# Qwiic_Shield_for_Teensy_Long.net
KiCad netlist of a schematic drawn in EAGLE
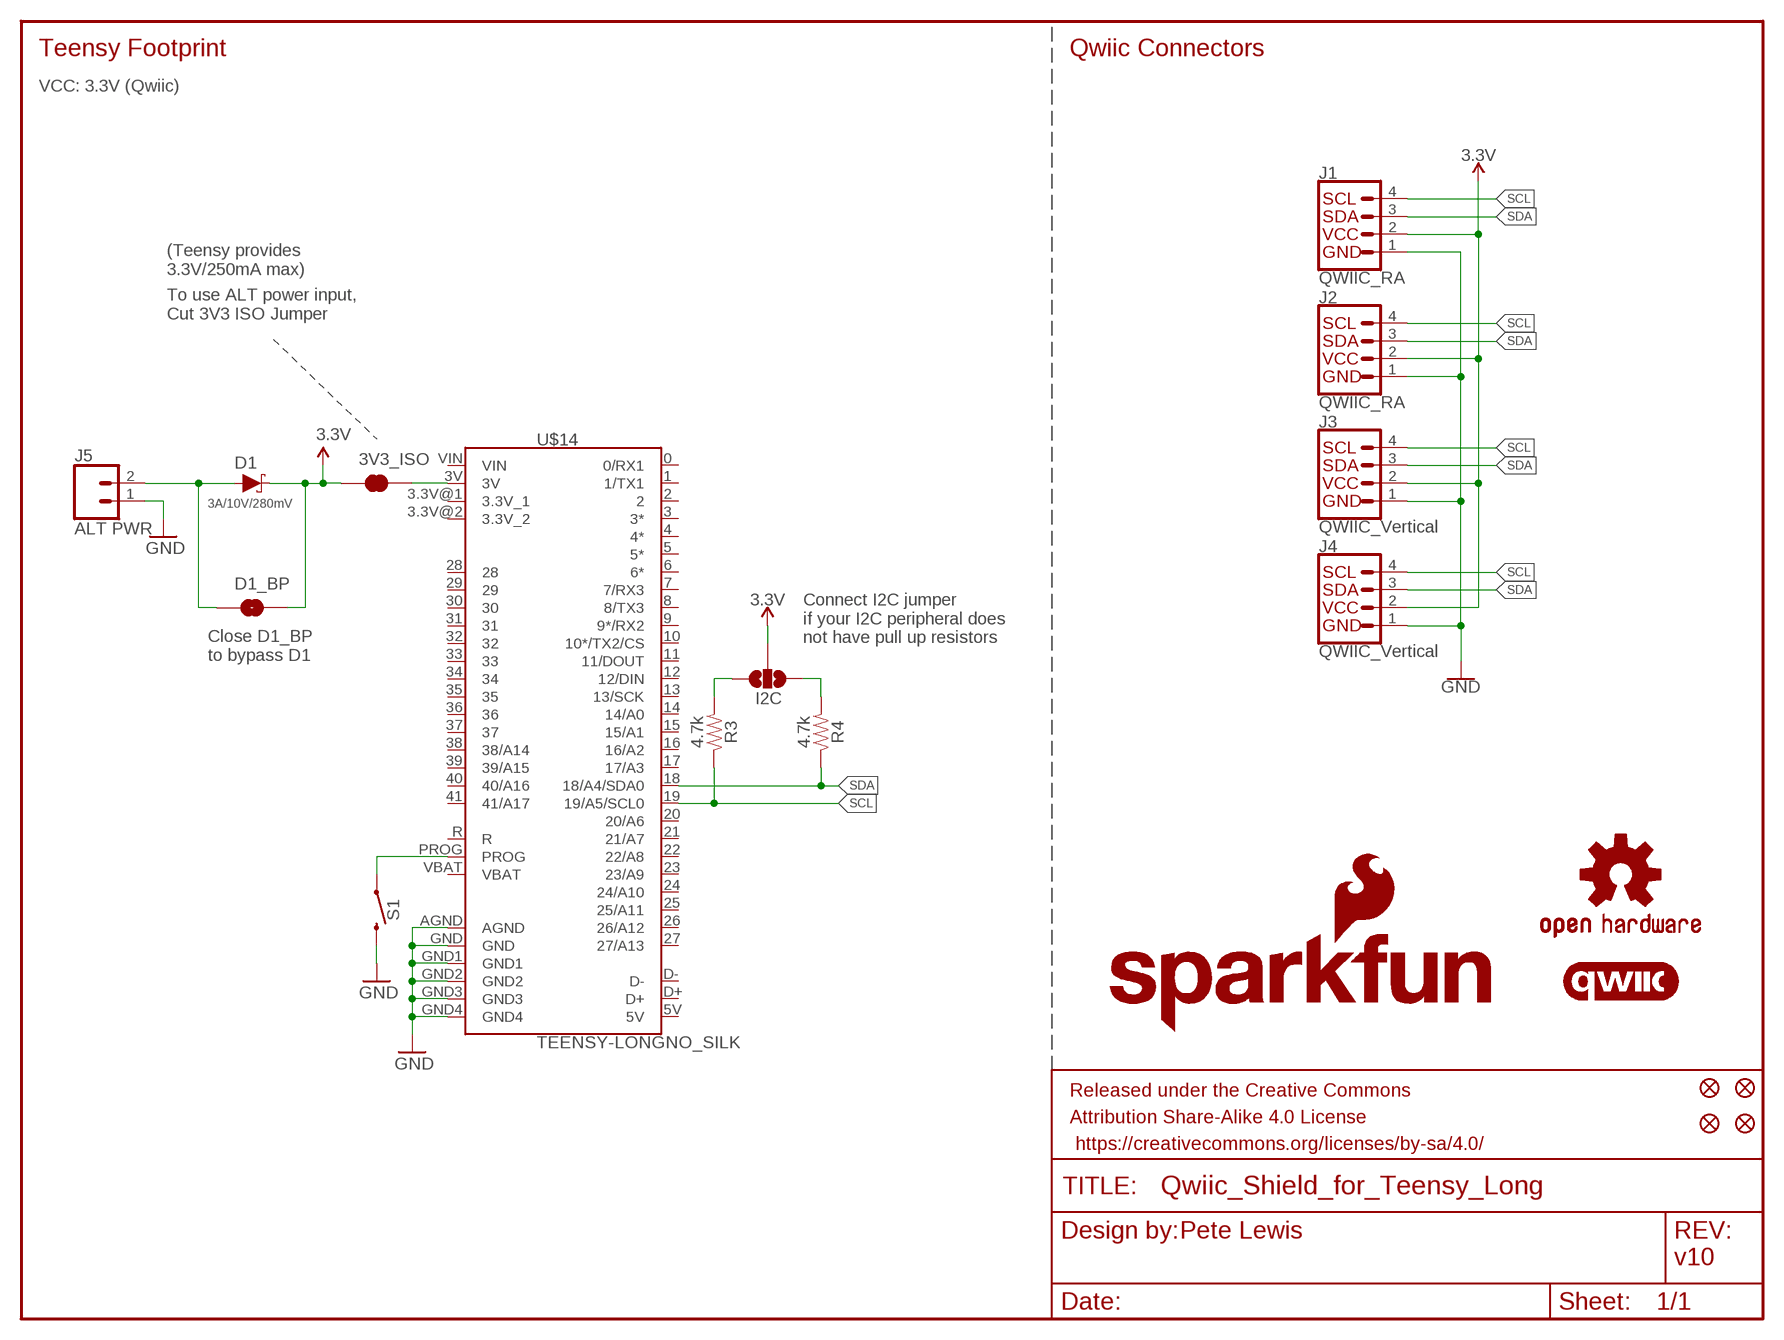
[diagram p0: schematic, sheet 1]

(export (version "E")
  (design (tool "Eeschema 10.0.6"))
  (components
    (comp (ref "3V3_ISO")
      (value "JUMPER-SMT_2_NC_TRACE_SILK")
      (footprint "eagle-import:SMT-JUMPER_2_NC_TRACE_SILK")
      (libsource (lib "eagle-import") (part "JUMPER-SMT_2_NC_TRACE_SILK"))
    )
    (comp (ref "D1")
      (value "3A/10V/280mV")
      (footprint "eagle-import:SOD-323")
      (libsource (lib "eagle-import") (part "DIODE-SCHOTTKY-BAT60A"))
    )
    (comp (ref "D1_BP")
      (value "JUMPER-SMT_2_NO_SILK")
      (footprint "eagle-import:SMT-JUMPER_2_NO_SILK")
      (libsource (lib "eagle-import") (part "JUMPER-SMT_2_NO_SILK"))
    )
    (comp (ref "FD1")
      (value "FIDUCIAL1X2")
      (footprint "eagle-import:FIDUCIAL-1X2")
      (libsource (lib "eagle-import") (part "FIDUCIAL1X2"))
    )
    (comp (ref "FD2")
      (value "FIDUCIAL1X2")
      (footprint "eagle-import:FIDUCIAL-1X2")
      (libsource (lib "eagle-import") (part "FIDUCIAL1X2"))
    )
    (comp (ref "FD3")
      (value "FIDUCIAL1X2")
      (footprint "eagle-import:FIDUCIAL-1X2")
      (libsource (lib "eagle-import") (part "FIDUCIAL1X2"))
    )
    (comp (ref "FD4")
      (value "FIDUCIAL1X2")
      (footprint "eagle-import:FIDUCIAL-1X2")
      (libsource (lib "eagle-import") (part "FIDUCIAL1X2"))
    )
    (comp (ref "FRAME1")
      (value "FRAME-LETTER")
      (footprint "eagle-import:CREATIVE_COMMONS")
      (libsource (lib "eagle-import") (part "FRAME-LETTER"))
    )
    (comp (ref "I2C")
      (value "JUMPER-SMT_3_NO_SILK")
      (footprint "eagle-import:SMT-JUMPER_3_NO_SILK")
      (libsource (lib "eagle-import") (part "JUMPER-SMT_3_NO_SILK"))
    )
    (comp (ref "J1")
      (value "QWIIC_RA")
      (footprint "eagle-import:JST04_1MM_RA")
      (libsource (lib "eagle-import") (part "QWIIC_CONNECTORJS-1MM"))
    )
    (comp (ref "J2")
      (value "QWIIC_RA")
      (footprint "eagle-import:JST04_1MM_RA")
      (libsource (lib "eagle-import") (part "QWIIC_CONNECTORJS-1MM"))
    )
    (comp (ref "J3")
      (value "QWIIC_Vertical")
      (footprint "eagle-import:JST04_1MM_VERT")
      (libsource (lib "eagle-import") (part "QWIIC_CONNECTOR"))
    )
    (comp (ref "J4")
      (value "QWIIC_Vertical")
      (footprint "eagle-import:JST04_1MM_VERT")
      (libsource (lib "eagle-import") (part "QWIIC_CONNECTOR"))
    )
    (comp (ref "J5")
      (value "ALT PWR")
      (footprint "eagle-import:1X02_NO_SILK")
      (libsource (lib "eagle-import") (part "CONN_021X02_NO_SILK"))
    )
    (comp (ref "LOGO1")
      (value "SFE_LOGO_NAME_FLAME.1_INCH")
      (footprint "eagle-import:SFE_LOGO_NAME_FLAME_.1")
      (libsource (lib "eagle-import") (part "SFE_LOGO_NAME_FLAME.1_INCH"))
    )
    (comp (ref "LOGO2")
      (value "SFE_LOGO_NAME_FLAME.1_INCH")
      (footprint "eagle-import:SFE_LOGO_NAME_FLAME_.1")
      (libsource (lib "eagle-import") (part "SFE_LOGO_NAME_FLAME.1_INCH"))
    )
    (comp (ref "LOGO3")
      (value "OSHW-LOGOS")
      (footprint "eagle-import:OSHW-LOGO-S")
      (libsource (lib "eagle-import") (part "OSHW-LOGOS"))
    )
    (comp (ref "LOGO4")
      (value "QWIIC_LOGO_5MM")
      (footprint "eagle-import:QWIIC_5MM")
      (libsource (lib "eagle-import") (part "QWIIC_LOGO_5MM"))
    )
    (comp (ref "LOGO5")
      (value "QWIIC_LOGO_5MM")
      (footprint "eagle-import:QWIIC_5MM")
      (libsource (lib "eagle-import") (part "QWIIC_LOGO_5MM"))
    )
    (comp (ref "R3")
      (value "4.7k")
      (footprint "eagle-import:0603")
      (libsource (lib "eagle-import") (part "4.7KOHM-0603-1/10W-1%"))
    )
    (comp (ref "R4")
      (value "4.7k")
      (footprint "eagle-import:0603")
      (libsource (lib "eagle-import") (part "4.7KOHM-0603-1/10W-1%"))
    )
    (comp (ref "S1")
      (value "MOMENTARY-SWITCH-SPST-SMD-5.2MM-TALL")
      (footprint "eagle-import:TACTILE_SWITCH_SMD_5.2MM")
      (libsource (lib "eagle-import") (part "MOMENTARY-SWITCH-SPST-SMD-5.2MM-TALL"))
    )
    (comp (ref "U$14")
      (value "TEENSY-LONGNO_SILK")
      (footprint "eagle-import:TEENSY-LONG_NO_SILK")
      (libsource (lib "eagle-import") (part "TEENSY-LONGNO_SILK"))
    )
  )
  (nets
    (net (code "1") (name "/3.3V_1") (class "Default")
      (node (ref "U$14") (pin "3.3V@1") (pinfunction "3.3V_1_3.3V@1") (pintype "power_in"))
    )
    (net (code "2") (name "/3.3V_2") (class "Default")
      (node (ref "U$14") (pin "3.3V@2") (pinfunction "3.3V_2_3.3V@2") (pintype "power_in"))
    )
    (net (code "3") (name "/5V") (class "Default")
      (node (ref "U$14") (pin "5V") (pinfunction "5V_5V") (pintype "power_in"))
    )
    (net (code "4") (name "/D+") (class "Default")
      (node (ref "U$14") (pin "D+") (pinfunction "D+_D+") (pintype "power_in"))
    )
    (net (code "5") (name "/D-") (class "Default")
      (node (ref "U$14") (pin "D-") (pinfunction "D-_D-") (pintype "power_in"))
    )
    (net (code "6") (name "/VBAT") (class "Default")
      (node (ref "U$14") (pin "VBAT") (pinfunction "VBAT_VBAT") (pintype "power_in"))
    )
    (net (code "7") (name "/VIN") (class "Default")
      (node (ref "U$14") (pin "VIN") (pinfunction "VIN_VIN") (pintype "power_in"))
    )
    (net (code "8") (name "3.3V") (class "Default")
      (node (ref "3V3_ISO") (pin "1") (pinfunction "1_1") (pintype "passive"))
      (node (ref "D1") (pin "C") (pinfunction "C_C") (pintype "passive"))
      (node (ref "D1_BP") (pin "2") (pinfunction "2_2") (pintype "passive"))
      (node (ref "I2C") (pin "2") (pinfunction "2_2") (pintype "passive"))
      (node (ref "J1") (pin "2") (pinfunction "2_2") (pintype "power_in"))
      (node (ref "J2") (pin "2") (pinfunction "2_2") (pintype "power_in"))
      (node (ref "J3") (pin "2") (pinfunction "2_2") (pintype "power_in"))
      (node (ref "J4") (pin "2") (pinfunction "2_2") (pintype "power_in"))
    )
    (net (code "9") (name "GND") (class "Default")
      (node (ref "J1") (pin "1") (pinfunction "1_1") (pintype "power_in"))
      (node (ref "J2") (pin "1") (pinfunction "1_1") (pintype "power_in"))
      (node (ref "J3") (pin "1") (pinfunction "1_1") (pintype "power_in"))
      (node (ref "J4") (pin "1") (pinfunction "1_1") (pintype "power_in"))
      (node (ref "J5") (pin "1") (pinfunction "1_1") (pintype "passive"))
      (node (ref "S1") (pin "3") (pinfunction "2_3") (pintype "passive"))
      (node (ref "U$14") (pin "AGND") (pinfunction "AGND_AGND") (pintype "power_in"))
      (node (ref "U$14") (pin "GND") (pinfunction "GND_GND") (pintype "power_in"))
      (node (ref "U$14") (pin "GND1") (pinfunction "GND1_GND1") (pintype "power_in"))
      (node (ref "U$14") (pin "GND2") (pinfunction "GND2_GND2") (pintype "power_in"))
      (node (ref "U$14") (pin "GND3") (pinfunction "GND3_GND3") (pintype "power_in"))
      (node (ref "U$14") (pin "GND4") (pinfunction "GND4_GND4") (pintype "bidirectional"))
    )
    (net (code "10") (name "Net-(3V3_ISO-Pad2)") (class "Default")
      (node (ref "3V3_ISO") (pin "2") (pinfunction "2_2") (pintype "passive"))
      (node (ref "U$14") (pin "3V") (pinfunction "3V_3V") (pintype "power_in"))
    )
    (net (code "11") (name "Net-(D1-PadA)") (class "Default")
      (node (ref "D1") (pin "A") (pinfunction "A_A") (pintype "passive"))
      (node (ref "D1_BP") (pin "1") (pinfunction "1_1") (pintype "passive"))
      (node (ref "J5") (pin "2") (pinfunction "2_2") (pintype "passive"))
    )
    (net (code "12") (name "Net-(I2C-Pad1)") (class "Default")
      (node (ref "I2C") (pin "1") (pinfunction "1_1") (pintype "passive"))
      (node (ref "R3") (pin "2") (pinfunction "2_2") (pintype "passive"))
    )
    (net (code "13") (name "Net-(I2C-Pad3)") (class "Default")
      (node (ref "I2C") (pin "3") (pinfunction "3_3") (pintype "passive"))
      (node (ref "R4") (pin "2") (pinfunction "2_2") (pintype "passive"))
    )
    (net (code "14") (name "Net-(S1-Pad1)") (class "Default")
      (node (ref "S1") (pin "1") (pinfunction "1_1") (pintype "passive"))
      (node (ref "U$14") (pin "PROG") (pinfunction "PROG_PROG") (pintype "bidirectional"))
    )
    (net (code "15") (name "SCL") (class "Default")
      (node (ref "J1") (pin "4") (pinfunction "4_4") (pintype "passive"))
      (node (ref "J2") (pin "4") (pinfunction "4_4") (pintype "passive"))
      (node (ref "J3") (pin "4") (pinfunction "4_4") (pintype "passive"))
      (node (ref "J4") (pin "4") (pinfunction "4_4") (pintype "passive"))
      (node (ref "R3") (pin "1") (pinfunction "1_1") (pintype "passive"))
      (node (ref "U$14") (pin "19") (pinfunction "19/A5/SCL0_19") (pintype "bidirectional"))
    )
    (net (code "16") (name "SDA") (class "Default")
      (node (ref "J1") (pin "3") (pinfunction "3_3") (pintype "passive"))
      (node (ref "J2") (pin "3") (pinfunction "3_3") (pintype "passive"))
      (node (ref "J3") (pin "3") (pinfunction "3_3") (pintype "passive"))
      (node (ref "J4") (pin "3") (pinfunction "3_3") (pintype "passive"))
      (node (ref "R4") (pin "1") (pinfunction "1_1") (pintype "passive"))
      (node (ref "U$14") (pin "18") (pinfunction "18/A4/SDA0_18") (pintype "bidirectional"))
    )
    (net (code "17") (name "unconnected-(U$14-0{slash}RX1-Pad0)") (class "Default")
      (node (ref "U$14") (pin "0") (pinfunction "0/RX1_0") (pintype "bidirectional"))
    )
    (net (code "18") (name "unconnected-(U$14-1{slash}TX1-Pad1)") (class "Default")
      (node (ref "U$14") (pin "1") (pinfunction "1/TX1_1") (pintype "bidirectional"))
    )
    (net (code "19") (name "unconnected-(U$14-3*-Pad3)") (class "Default")
      (node (ref "U$14") (pin "3") (pinfunction "3*_3") (pintype "bidirectional"))
    )
    (net (code "20") (name "unconnected-(U$14-4*-Pad4)") (class "Default")
      (node (ref "U$14") (pin "4") (pinfunction "4*_4") (pintype "bidirectional"))
    )
    (net (code "21") (name "unconnected-(U$14-5*-Pad5)") (class "Default")
      (node (ref "U$14") (pin "5") (pinfunction "5*_5") (pintype "bidirectional"))
    )
    (net (code "22") (name "unconnected-(U$14-6*-Pad6)") (class "Default")
      (node (ref "U$14") (pin "6") (pinfunction "6*_6") (pintype "bidirectional"))
    )
    (net (code "23") (name "unconnected-(U$14-7{slash}RX3-Pad7)") (class "Default")
      (node (ref "U$14") (pin "7") (pinfunction "7/RX3_7") (pintype "bidirectional"))
    )
    (net (code "24") (name "unconnected-(U$14-8{slash}TX3-Pad8)") (class "Default")
      (node (ref "U$14") (pin "8") (pinfunction "8/TX3_8") (pintype "bidirectional"))
    )
    (net (code "25") (name "unconnected-(U$14-9*{slash}RX2-Pad9)") (class "Default")
      (node (ref "U$14") (pin "9") (pinfunction "9*/RX2_9") (pintype "bidirectional"))
    )
    (net (code "26") (name "unconnected-(U$14-10*{slash}TX2{slash}CS-Pad10)") (class "Default")
      (node (ref "U$14") (pin "10") (pinfunction "10*/TX2/CS_10") (pintype "bidirectional"))
    )
    (net (code "27") (name "unconnected-(U$14-11{slash}DOUT-Pad11)") (class "Default")
      (node (ref "U$14") (pin "11") (pinfunction "11/DOUT_11") (pintype "bidirectional"))
    )
    (net (code "28") (name "unconnected-(U$14-12{slash}DIN-Pad12)") (class "Default")
      (node (ref "U$14") (pin "12") (pinfunction "12/DIN_12") (pintype "bidirectional"))
    )
    (net (code "29") (name "unconnected-(U$14-13{slash}SCK-Pad13)") (class "Default")
      (node (ref "U$14") (pin "13") (pinfunction "13/SCK_13") (pintype "bidirectional"))
    )
    (net (code "30") (name "unconnected-(U$14-14{slash}A0-Pad14)") (class "Default")
      (node (ref "U$14") (pin "14") (pinfunction "14/A0_14") (pintype "bidirectional"))
    )
    (net (code "31") (name "unconnected-(U$14-15{slash}A1-Pad15)") (class "Default")
      (node (ref "U$14") (pin "15") (pinfunction "15/A1_15") (pintype "bidirectional"))
    )
    (net (code "32") (name "unconnected-(U$14-16{slash}A2-Pad16)") (class "Default")
      (node (ref "U$14") (pin "16") (pinfunction "16/A2_16") (pintype "bidirectional"))
    )
    (net (code "33") (name "unconnected-(U$14-17{slash}A3-Pad17)") (class "Default")
      (node (ref "U$14") (pin "17") (pinfunction "17/A3_17") (pintype "bidirectional"))
    )
    (net (code "34") (name "unconnected-(U$14-20{slash}A6-Pad20)") (class "Default")
      (node (ref "U$14") (pin "20") (pinfunction "20/A6_20") (pintype "bidirectional"))
    )
    (net (code "35") (name "unconnected-(U$14-21{slash}A7-Pad21)") (class "Default")
      (node (ref "U$14") (pin "21") (pinfunction "21/A7_21") (pintype "bidirectional"))
    )
    (net (code "36") (name "unconnected-(U$14-22{slash}A8-Pad22)") (class "Default")
      (node (ref "U$14") (pin "22") (pinfunction "22/A8_22") (pintype "bidirectional"))
    )
    (net (code "37") (name "unconnected-(U$14-23{slash}A9-Pad23)") (class "Default")
      (node (ref "U$14") (pin "23") (pinfunction "23/A9_23") (pintype "bidirectional"))
    )
    (net (code "38") (name "unconnected-(U$14-24{slash}A10-Pad24)") (class "Default")
      (node (ref "U$14") (pin "24") (pinfunction "24/A10_24") (pintype "bidirectional"))
    )
    (net (code "39") (name "unconnected-(U$14-25{slash}A11-Pad25)") (class "Default")
      (node (ref "U$14") (pin "25") (pinfunction "25/A11_25") (pintype "bidirectional"))
    )
    (net (code "40") (name "unconnected-(U$14-26{slash}A12-Pad26)") (class "Default")
      (node (ref "U$14") (pin "26") (pinfunction "26/A12_26") (pintype "bidirectional"))
    )
    (net (code "41") (name "unconnected-(U$14-27{slash}A13-Pad27)") (class "Default")
      (node (ref "U$14") (pin "27") (pinfunction "27/A13_27") (pintype "bidirectional"))
    )
    (net (code "42") (name "unconnected-(U$14-38{slash}A14-Pad38)") (class "Default")
      (node (ref "U$14") (pin "38") (pinfunction "38/A14_38") (pintype "bidirectional"))
    )
    (net (code "43") (name "unconnected-(U$14-39{slash}A15-Pad39)") (class "Default")
      (node (ref "U$14") (pin "39") (pinfunction "39/A15_39") (pintype "bidirectional"))
    )
    (net (code "44") (name "unconnected-(U$14-40{slash}A16-Pad40)") (class "Default")
      (node (ref "U$14") (pin "40") (pinfunction "40/A16_40") (pintype "bidirectional"))
    )
    (net (code "45") (name "unconnected-(U$14-41{slash}A17-Pad41)") (class "Default")
      (node (ref "U$14") (pin "41") (pinfunction "41/A17_41") (pintype "bidirectional"))
    )
    (net (code "46") (name "unconnected-(U$14-Pad2)") (class "Default")
      (node (ref "U$14") (pin "2") (pinfunction "2_2") (pintype "bidirectional"))
    )
    (net (code "47") (name "unconnected-(U$14-Pad28)") (class "Default")
      (node (ref "U$14") (pin "28") (pinfunction "28_28") (pintype "bidirectional"))
    )
    (net (code "48") (name "unconnected-(U$14-Pad29)") (class "Default")
      (node (ref "U$14") (pin "29") (pinfunction "29_29") (pintype "bidirectional"))
    )
    (net (code "49") (name "unconnected-(U$14-Pad30)") (class "Default")
      (node (ref "U$14") (pin "30") (pinfunction "30_30") (pintype "bidirectional"))
    )
    (net (code "50") (name "unconnected-(U$14-Pad31)") (class "Default")
      (node (ref "U$14") (pin "31") (pinfunction "31_31") (pintype "bidirectional"))
    )
    (net (code "51") (name "unconnected-(U$14-Pad32)") (class "Default")
      (node (ref "U$14") (pin "32") (pinfunction "32_32") (pintype "bidirectional"))
    )
    (net (code "52") (name "unconnected-(U$14-Pad33)") (class "Default")
      (node (ref "U$14") (pin "33") (pinfunction "33_33") (pintype "bidirectional"))
    )
    (net (code "53") (name "unconnected-(U$14-Pad34)") (class "Default")
      (node (ref "U$14") (pin "34") (pinfunction "34_34") (pintype "bidirectional"))
    )
    (net (code "54") (name "unconnected-(U$14-Pad35)") (class "Default")
      (node (ref "U$14") (pin "35") (pinfunction "35_35") (pintype "bidirectional"))
    )
    (net (code "55") (name "unconnected-(U$14-Pad36)") (class "Default")
      (node (ref "U$14") (pin "36") (pinfunction "36_36") (pintype "bidirectional"))
    )
    (net (code "56") (name "unconnected-(U$14-Pad37)") (class "Default")
      (node (ref "U$14") (pin "37") (pinfunction "37_37") (pintype "bidirectional"))
    )
    (net (code "57") (name "unconnected-(U$14-PadR)") (class "Default")
      (node (ref "U$14") (pin "R") (pinfunction "R_R") (pintype "bidirectional"))
    )
  )
)
